# nola1.net
KiCad netlist of a schematic drawn in EAGLE
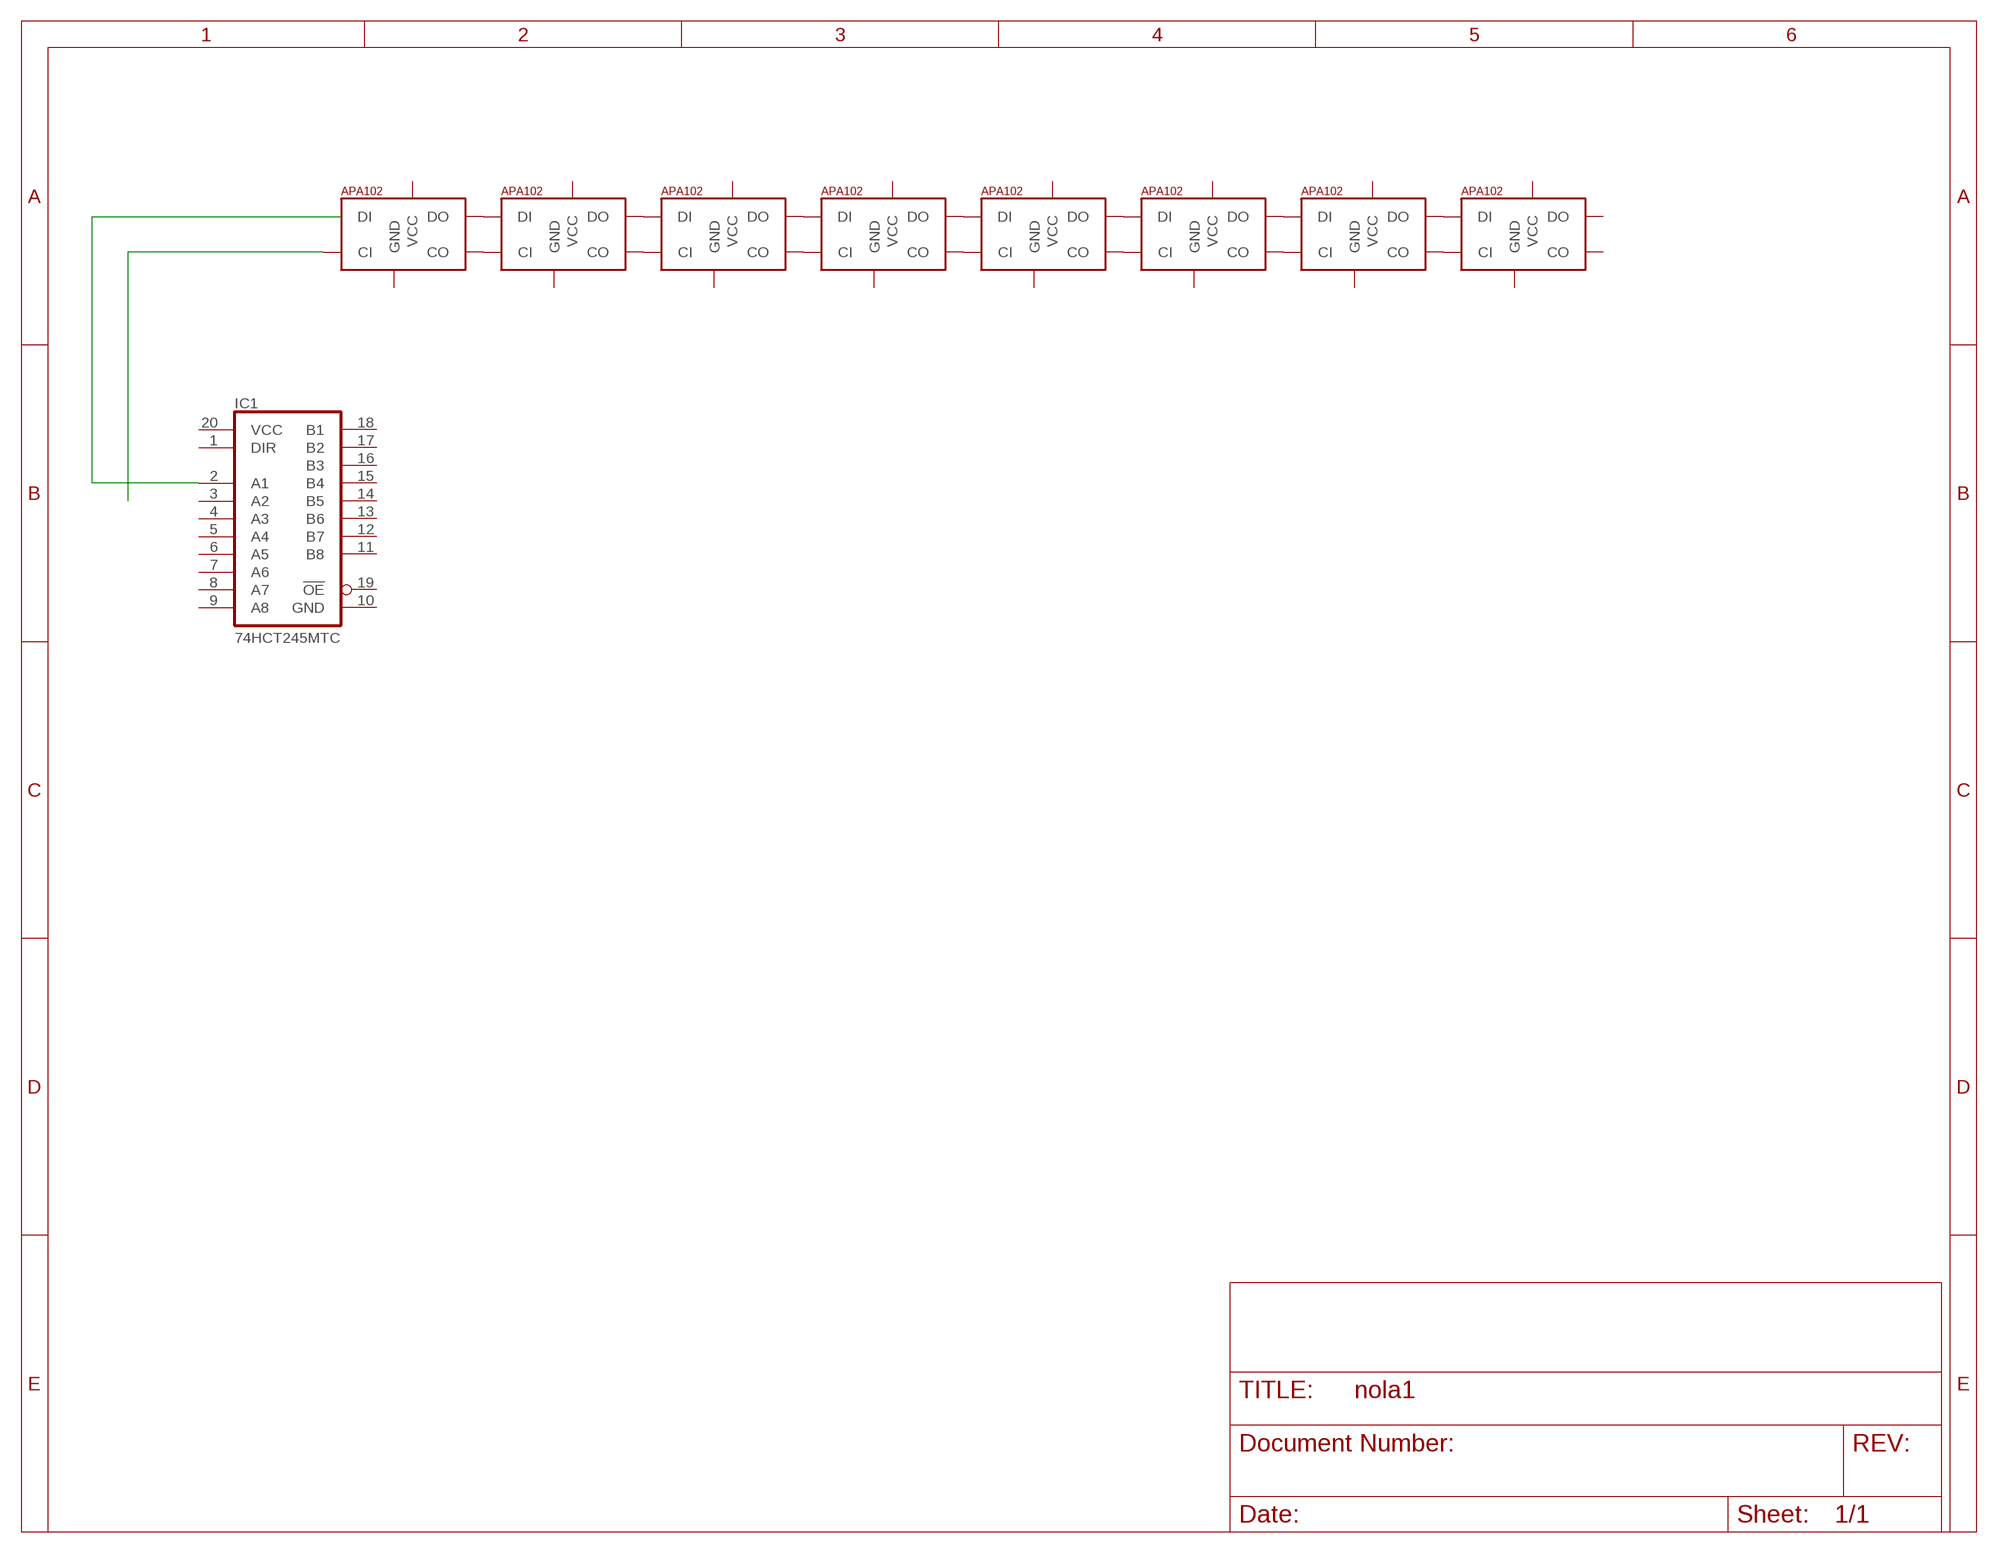
[diagram p0: schematic, sheet 1]

(export (version "E")
  (design (tool "Eeschema 10.0.6"))
  (components
    (comp (ref "IC1")
      (value "74HCT245MTC")
      (footprint "eagle-import:SSOP20")
      (libsource (lib "eagle-import") (part "74HCT245MTC"))
    )
    (comp (ref "U$3")
      (value "APA1025050")
      (footprint "eagle-import:APA102_5050")
      (libsource (lib "eagle-import") (part "APA1025050"))
    )
    (comp (ref "U$4")
      (value "APA1025050")
      (footprint "eagle-import:APA102_5050")
      (libsource (lib "eagle-import") (part "APA1025050"))
    )
    (comp (ref "U$5")
      (value "APA1025050")
      (footprint "eagle-import:APA102_5050")
      (libsource (lib "eagle-import") (part "APA1025050"))
    )
    (comp (ref "U$6")
      (value "APA1025050")
      (footprint "eagle-import:APA102_5050")
      (libsource (lib "eagle-import") (part "APA1025050"))
    )
    (comp (ref "U$7")
      (value "APA1025050")
      (footprint "eagle-import:APA102_5050")
      (libsource (lib "eagle-import") (part "APA1025050"))
    )
    (comp (ref "U$8")
      (value "APA1025050")
      (footprint "eagle-import:APA102_5050")
      (libsource (lib "eagle-import") (part "APA1025050"))
    )
    (comp (ref "U$9")
      (value "APA1025050")
      (footprint "eagle-import:APA102_5050")
      (libsource (lib "eagle-import") (part "APA1025050"))
    )
    (comp (ref "U$10")
      (value "APA1025050")
      (footprint "eagle-import:APA102_5050")
      (libsource (lib "eagle-import") (part "APA1025050"))
    )
  )
  (nets
    (net (code "1") (name "/GND") (class "Default")
      (node (ref "IC1") (pin "10") (pinfunction "GND_10") (pintype "power_in"))
    )
    (net (code "2") (name "/VCC") (class "Default")
      (node (ref "IC1") (pin "20") (pinfunction "VCC_20") (pintype "power_in"))
    )
    (net (code "3") (name "Net-(U$3-CO)") (class "Default")
      (node (ref "U$3") (pin "2") (pinfunction "CO_2") (pintype "bidirectional"))
      (node (ref "U$4") (pin "5") (pinfunction "CI_5") (pintype "bidirectional"))
    )
    (net (code "4") (name "Net-(U$3-DO)") (class "Default")
      (node (ref "U$3") (pin "3") (pinfunction "DO_3") (pintype "bidirectional"))
      (node (ref "U$4") (pin "4") (pinfunction "DI_4") (pintype "bidirectional"))
    )
    (net (code "5") (name "Net-(U$4-CO)") (class "Default")
      (node (ref "U$4") (pin "2") (pinfunction "CO_2") (pintype "bidirectional"))
      (node (ref "U$5") (pin "5") (pinfunction "CI_5") (pintype "bidirectional"))
    )
    (net (code "6") (name "Net-(U$4-DO)") (class "Default")
      (node (ref "U$4") (pin "3") (pinfunction "DO_3") (pintype "bidirectional"))
      (node (ref "U$5") (pin "4") (pinfunction "DI_4") (pintype "bidirectional"))
    )
    (net (code "7") (name "Net-(U$5-CO)") (class "Default")
      (node (ref "U$5") (pin "2") (pinfunction "CO_2") (pintype "bidirectional"))
      (node (ref "U$6") (pin "5") (pinfunction "CI_5") (pintype "bidirectional"))
    )
    (net (code "8") (name "Net-(U$5-DO)") (class "Default")
      (node (ref "U$5") (pin "3") (pinfunction "DO_3") (pintype "bidirectional"))
      (node (ref "U$6") (pin "4") (pinfunction "DI_4") (pintype "bidirectional"))
    )
    (net (code "9") (name "Net-(U$6-CO)") (class "Default")
      (node (ref "U$6") (pin "2") (pinfunction "CO_2") (pintype "bidirectional"))
      (node (ref "U$7") (pin "5") (pinfunction "CI_5") (pintype "bidirectional"))
    )
    (net (code "10") (name "Net-(U$6-DO)") (class "Default")
      (node (ref "U$6") (pin "3") (pinfunction "DO_3") (pintype "bidirectional"))
      (node (ref "U$7") (pin "4") (pinfunction "DI_4") (pintype "bidirectional"))
    )
    (net (code "11") (name "Net-(U$7-CO)") (class "Default")
      (node (ref "U$7") (pin "2") (pinfunction "CO_2") (pintype "bidirectional"))
      (node (ref "U$8") (pin "5") (pinfunction "CI_5") (pintype "bidirectional"))
    )
    (net (code "12") (name "Net-(U$7-DO)") (class "Default")
      (node (ref "U$7") (pin "3") (pinfunction "DO_3") (pintype "bidirectional"))
      (node (ref "U$8") (pin "4") (pinfunction "DI_4") (pintype "bidirectional"))
    )
    (net (code "13") (name "Net-(U$8-CO)") (class "Default")
      (node (ref "U$8") (pin "2") (pinfunction "CO_2") (pintype "bidirectional"))
      (node (ref "U$9") (pin "5") (pinfunction "CI_5") (pintype "bidirectional"))
    )
    (net (code "14") (name "Net-(U$8-DO)") (class "Default")
      (node (ref "U$8") (pin "3") (pinfunction "DO_3") (pintype "bidirectional"))
      (node (ref "U$9") (pin "4") (pinfunction "DI_4") (pintype "bidirectional"))
    )
    (net (code "15") (name "Net-(U$10-CI)") (class "Default")
      (node (ref "U$10") (pin "5") (pinfunction "CI_5") (pintype "bidirectional"))
      (node (ref "U$9") (pin "2") (pinfunction "CO_2") (pintype "bidirectional"))
    )
    (net (code "16") (name "Net-(U$10-DI)") (class "Default")
      (node (ref "U$10") (pin "4") (pinfunction "DI_4") (pintype "bidirectional"))
      (node (ref "U$9") (pin "3") (pinfunction "DO_3") (pintype "bidirectional"))
    )
    (net (code "17") (name "unconnected-(IC1-A1-Pad2)") (class "Default")
      (node (ref "IC1") (pin "2") (pinfunction "A1_2") (pintype "bidirectional"))
    )
    (net (code "18") (name "unconnected-(IC1-A2-Pad3)") (class "Default")
      (node (ref "IC1") (pin "3") (pinfunction "A2_3") (pintype "bidirectional"))
    )
    (net (code "19") (name "unconnected-(IC1-A3-Pad4)") (class "Default")
      (node (ref "IC1") (pin "4") (pinfunction "A3_4") (pintype "bidirectional"))
    )
    (net (code "20") (name "unconnected-(IC1-A4-Pad5)") (class "Default")
      (node (ref "IC1") (pin "5") (pinfunction "A4_5") (pintype "bidirectional"))
    )
    (net (code "21") (name "unconnected-(IC1-A5-Pad6)") (class "Default")
      (node (ref "IC1") (pin "6") (pinfunction "A5_6") (pintype "bidirectional"))
    )
    (net (code "22") (name "unconnected-(IC1-A6-Pad7)") (class "Default")
      (node (ref "IC1") (pin "7") (pinfunction "A6_7") (pintype "bidirectional"))
    )
    (net (code "23") (name "unconnected-(IC1-A7-Pad8)") (class "Default")
      (node (ref "IC1") (pin "8") (pinfunction "A7_8") (pintype "bidirectional"))
    )
    (net (code "24") (name "unconnected-(IC1-A8-Pad9)") (class "Default")
      (node (ref "IC1") (pin "9") (pinfunction "A8_9") (pintype "bidirectional"))
    )
    (net (code "25") (name "unconnected-(IC1-B1-Pad18)") (class "Default")
      (node (ref "IC1") (pin "18") (pinfunction "B1_18") (pintype "bidirectional"))
    )
    (net (code "26") (name "unconnected-(IC1-B2-Pad17)") (class "Default")
      (node (ref "IC1") (pin "17") (pinfunction "B2_17") (pintype "bidirectional"))
    )
    (net (code "27") (name "unconnected-(IC1-B3-Pad16)") (class "Default")
      (node (ref "IC1") (pin "16") (pinfunction "B3_16") (pintype "bidirectional"))
    )
    (net (code "28") (name "unconnected-(IC1-B4-Pad15)") (class "Default")
      (node (ref "IC1") (pin "15") (pinfunction "B4_15") (pintype "bidirectional"))
    )
    (net (code "29") (name "unconnected-(IC1-B5-Pad14)") (class "Default")
      (node (ref "IC1") (pin "14") (pinfunction "B5_14") (pintype "bidirectional"))
    )
    (net (code "30") (name "unconnected-(IC1-B6-Pad13)") (class "Default")
      (node (ref "IC1") (pin "13") (pinfunction "B6_13") (pintype "bidirectional"))
    )
    (net (code "31") (name "unconnected-(IC1-B7-Pad12)") (class "Default")
      (node (ref "IC1") (pin "12") (pinfunction "B7_12") (pintype "bidirectional"))
    )
    (net (code "32") (name "unconnected-(IC1-B8-Pad11)") (class "Default")
      (node (ref "IC1") (pin "11") (pinfunction "B8_11") (pintype "bidirectional"))
    )
    (net (code "33") (name "unconnected-(IC1-DIR-Pad1)") (class "Default")
      (node (ref "IC1") (pin "1") (pinfunction "DIR_1") (pintype "input"))
    )
    (net (code "34") (name "unconnected-(IC1-~{OE}-Pad19)") (class "Default")
      (node (ref "IC1") (pin "19") (pinfunction "~{OE}_19") (pintype "input"))
    )
    (net (code "35") (name "unconnected-(U$3-CI-Pad5)") (class "Default")
      (node (ref "U$3") (pin "5") (pinfunction "CI_5") (pintype "bidirectional"))
    )
    (net (code "36") (name "unconnected-(U$3-DI-Pad4)") (class "Default")
      (node (ref "U$3") (pin "4") (pinfunction "DI_4") (pintype "bidirectional"))
    )
    (net (code "37") (name "unconnected-(U$3-GND-Pad6)") (class "Default")
      (node (ref "U$3") (pin "6") (pinfunction "GND_6") (pintype "bidirectional"))
    )
    (net (code "38") (name "unconnected-(U$3-VCC-Pad1)") (class "Default")
      (node (ref "U$3") (pin "1") (pinfunction "VCC_1") (pintype "bidirectional"))
    )
    (net (code "39") (name "unconnected-(U$4-GND-Pad6)") (class "Default")
      (node (ref "U$4") (pin "6") (pinfunction "GND_6") (pintype "bidirectional"))
    )
    (net (code "40") (name "unconnected-(U$4-VCC-Pad1)") (class "Default")
      (node (ref "U$4") (pin "1") (pinfunction "VCC_1") (pintype "bidirectional"))
    )
    (net (code "41") (name "unconnected-(U$5-GND-Pad6)") (class "Default")
      (node (ref "U$5") (pin "6") (pinfunction "GND_6") (pintype "bidirectional"))
    )
    (net (code "42") (name "unconnected-(U$5-VCC-Pad1)") (class "Default")
      (node (ref "U$5") (pin "1") (pinfunction "VCC_1") (pintype "bidirectional"))
    )
    (net (code "43") (name "unconnected-(U$6-GND-Pad6)") (class "Default")
      (node (ref "U$6") (pin "6") (pinfunction "GND_6") (pintype "bidirectional"))
    )
    (net (code "44") (name "unconnected-(U$6-VCC-Pad1)") (class "Default")
      (node (ref "U$6") (pin "1") (pinfunction "VCC_1") (pintype "bidirectional"))
    )
    (net (code "45") (name "unconnected-(U$7-GND-Pad6)") (class "Default")
      (node (ref "U$7") (pin "6") (pinfunction "GND_6") (pintype "bidirectional"))
    )
    (net (code "46") (name "unconnected-(U$7-VCC-Pad1)") (class "Default")
      (node (ref "U$7") (pin "1") (pinfunction "VCC_1") (pintype "bidirectional"))
    )
    (net (code "47") (name "unconnected-(U$8-GND-Pad6)") (class "Default")
      (node (ref "U$8") (pin "6") (pinfunction "GND_6") (pintype "bidirectional"))
    )
    (net (code "48") (name "unconnected-(U$8-VCC-Pad1)") (class "Default")
      (node (ref "U$8") (pin "1") (pinfunction "VCC_1") (pintype "bidirectional"))
    )
    (net (code "49") (name "unconnected-(U$9-GND-Pad6)") (class "Default")
      (node (ref "U$9") (pin "6") (pinfunction "GND_6") (pintype "bidirectional"))
    )
    (net (code "50") (name "unconnected-(U$9-VCC-Pad1)") (class "Default")
      (node (ref "U$9") (pin "1") (pinfunction "VCC_1") (pintype "bidirectional"))
    )
    (net (code "51") (name "unconnected-(U$10-CO-Pad2)") (class "Default")
      (node (ref "U$10") (pin "2") (pinfunction "CO_2") (pintype "bidirectional"))
    )
    (net (code "52") (name "unconnected-(U$10-DO-Pad3)") (class "Default")
      (node (ref "U$10") (pin "3") (pinfunction "DO_3") (pintype "bidirectional"))
    )
    (net (code "53") (name "unconnected-(U$10-GND-Pad6)") (class "Default")
      (node (ref "U$10") (pin "6") (pinfunction "GND_6") (pintype "bidirectional"))
    )
    (net (code "54") (name "unconnected-(U$10-VCC-Pad1)") (class "Default")
      (node (ref "U$10") (pin "1") (pinfunction "VCC_1") (pintype "bidirectional"))
    )
  )
)
